# schematic-incomplete.net
KiCad netlist of a schematic drawn in EAGLE
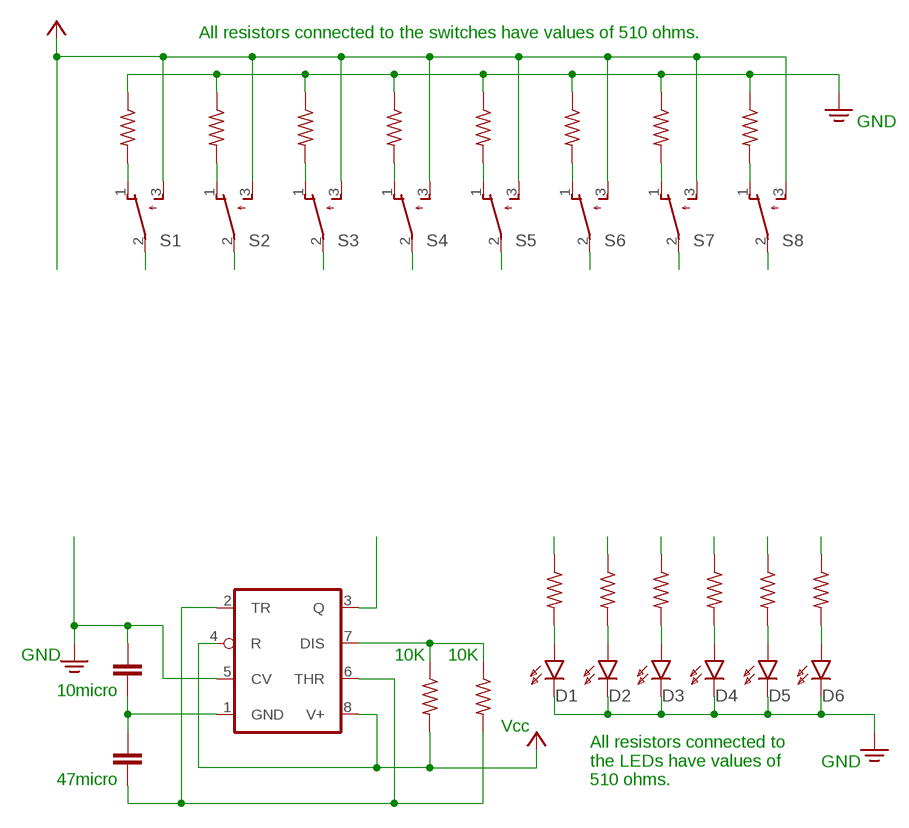
[diagram p0: schematic, sheet 1]

(export (version "E")
  (design (tool "Eeschema 10.0.6"))
  (components
    (comp (ref "10K")
      (value "R-US_0204/7")
      (footprint "eagle-import:0204_7")
      (libsource (lib "eagle-import") (part "R-US_0204/7"))
    )
    (comp (ref "CX1")
      (value "CXXC15B8")
      (footprint "eagle-import:XC15B8")
      (libsource (lib "eagle-import") (part "CXXC15B8"))
    )
    (comp (ref "CX2")
      (value "CXXC15B8")
      (footprint "eagle-import:XC15B8")
      (libsource (lib "eagle-import") (part "CXXC15B8"))
    )
    (comp (ref "D1")
      (value "HLMP6")
      (footprint "eagle-import:HLMP6")
      (fields (field (name "MF") "AGILENT TECHNOLOGIES") (field (name "MPN") "HLMP-6500"))
      (libsource (lib "eagle-import") (part "HLMP6"))
    )
    (comp (ref "D2")
      (value "HLMP6")
      (footprint "eagle-import:HLMP6")
      (fields (field (name "MF") "AGILENT TECHNOLOGIES") (field (name "MPN") "HLMP-6500"))
      (libsource (lib "eagle-import") (part "HLMP6"))
    )
    (comp (ref "D3")
      (value "HLMP6")
      (footprint "eagle-import:HLMP6")
      (fields (field (name "MF") "AGILENT TECHNOLOGIES") (field (name "MPN") "HLMP-6500"))
      (libsource (lib "eagle-import") (part "HLMP6"))
    )
    (comp (ref "D4")
      (value "HLMP6")
      (footprint "eagle-import:HLMP6")
      (fields (field (name "MF") "AGILENT TECHNOLOGIES") (field (name "MPN") "HLMP-6500"))
      (libsource (lib "eagle-import") (part "HLMP6"))
    )
    (comp (ref "D5")
      (value "HLMP6")
      (footprint "eagle-import:HLMP6")
      (fields (field (name "MF") "AGILENT TECHNOLOGIES") (field (name "MPN") "HLMP-6500"))
      (libsource (lib "eagle-import") (part "HLMP6"))
    )
    (comp (ref "D6")
      (value "HLMP6")
      (footprint "eagle-import:HLMP6")
      (fields (field (name "MF") "AGILENT TECHNOLOGIES") (field (name "MPN") "HLMP-6500"))
      (libsource (lib "eagle-import") (part "HLMP6"))
    )
    (comp (ref "IC1")
      (value "LM555N")
      (footprint "eagle-import:DIL08")
      (libsource (lib "eagle-import") (part "555NLM"))
    )
    (comp (ref "R1")
      (value "R-US_0204/7")
      (footprint "eagle-import:0204_7")
      (libsource (lib "eagle-import") (part "R-US_0204/7"))
    )
    (comp (ref "R2")
      (value "R-US_0204/7")
      (footprint "eagle-import:0204_7")
      (libsource (lib "eagle-import") (part "R-US_0204/7"))
    )
    (comp (ref "R3")
      (value "R-US_0204/7")
      (footprint "eagle-import:0204_7")
      (libsource (lib "eagle-import") (part "R-US_0204/7"))
    )
    (comp (ref "R4")
      (value "R-US_0204/7")
      (footprint "eagle-import:0204_7")
      (libsource (lib "eagle-import") (part "R-US_0204/7"))
    )
    (comp (ref "R5")
      (value "R-US_0204/7")
      (footprint "eagle-import:0204_7")
      (libsource (lib "eagle-import") (part "R-US_0204/7"))
    )
    (comp (ref "R6")
      (value "R-US_0204/7")
      (footprint "eagle-import:0204_7")
      (libsource (lib "eagle-import") (part "R-US_0204/7"))
    )
    (comp (ref "R7")
      (value "R-US_0204/7")
      (footprint "eagle-import:0204_7")
      (libsource (lib "eagle-import") (part "R-US_0204/7"))
    )
    (comp (ref "R8")
      (value "R-US_0204/7")
      (footprint "eagle-import:0204_7")
      (libsource (lib "eagle-import") (part "R-US_0204/7"))
    )
    (comp (ref "R9")
      (value "R-US_0204/7")
      (footprint "eagle-import:0204_7")
      (libsource (lib "eagle-import") (part "R-US_0204/7"))
    )
    (comp (ref "R10")
      (value "R-US_0204/7")
      (footprint "eagle-import:0204_7")
      (libsource (lib "eagle-import") (part "R-US_0204/7"))
    )
    (comp (ref "R11")
      (value "R-US_0204/7")
      (footprint "eagle-import:0204_7")
      (libsource (lib "eagle-import") (part "R-US_0204/7"))
    )
    (comp (ref "R12")
      (value "R-US_0204/7")
      (footprint "eagle-import:0204_7")
      (libsource (lib "eagle-import") (part "R-US_0204/7"))
    )
    (comp (ref "R13")
      (value "R-US_0204/7")
      (footprint "eagle-import:0204_7")
      (libsource (lib "eagle-import") (part "R-US_0204/7"))
    )
    (comp (ref "R14")
      (value "R-US_0204/7")
      (footprint "eagle-import:0204_7")
      (libsource (lib "eagle-import") (part "R-US_0204/7"))
    )
    (comp (ref "R15")
      (value "R-US_0204/7")
      (footprint "eagle-import:0204_7")
      (libsource (lib "eagle-import") (part "R-US_0204/7"))
    )
    (comp (ref "S1")
      (value "TL32PO")
      (footprint "eagle-import:TL3XPO")
      (libsource (lib "eagle-import") (part "TL32PO"))
    )
    (comp (ref "S2")
      (value "TL32PO")
      (footprint "eagle-import:TL3XPO")
      (libsource (lib "eagle-import") (part "TL32PO"))
    )
    (comp (ref "S3")
      (value "TL32PO")
      (footprint "eagle-import:TL3XPO")
      (libsource (lib "eagle-import") (part "TL32PO"))
    )
    (comp (ref "S4")
      (value "TL32PO")
      (footprint "eagle-import:TL3XPO")
      (libsource (lib "eagle-import") (part "TL32PO"))
    )
    (comp (ref "S5")
      (value "TL32PO")
      (footprint "eagle-import:TL3XPO")
      (libsource (lib "eagle-import") (part "TL32PO"))
    )
    (comp (ref "S6")
      (value "TL32PO")
      (footprint "eagle-import:TL3XPO")
      (libsource (lib "eagle-import") (part "TL32PO"))
    )
    (comp (ref "S7")
      (value "TL32PO")
      (footprint "eagle-import:TL3XPO")
      (libsource (lib "eagle-import") (part "TL32PO"))
    )
    (comp (ref "S8")
      (value "TL32PO")
      (footprint "eagle-import:TL3XPO")
      (libsource (lib "eagle-import") (part "TL32PO"))
    )
  )
  (nets
    (net (code "1") (name "Net-(D1-PadA)") (class "Default")
      (node (ref "D1") (pin "A") (pinfunction "A_A") (pintype "passive"))
      (node (ref "R10") (pin "2") (pinfunction "2_2") (pintype "passive"))
    )
    (net (code "2") (name "Net-(D2-PadA)") (class "Default")
      (node (ref "D2") (pin "A") (pinfunction "A_A") (pintype "passive"))
      (node (ref "R11") (pin "2") (pinfunction "2_2") (pintype "passive"))
    )
    (net (code "3") (name "Net-(D3-PadA)") (class "Default")
      (node (ref "D3") (pin "A") (pinfunction "A_A") (pintype "passive"))
      (node (ref "R12") (pin "2") (pinfunction "2_2") (pintype "passive"))
    )
    (net (code "4") (name "Net-(D4-PadA)") (class "Default")
      (node (ref "D4") (pin "A") (pinfunction "A_A") (pintype "passive"))
      (node (ref "R13") (pin "2") (pinfunction "2_2") (pintype "passive"))
    )
    (net (code "5") (name "Net-(D5-PadA)") (class "Default")
      (node (ref "D5") (pin "A") (pinfunction "A_A") (pintype "passive"))
      (node (ref "R14") (pin "2") (pinfunction "2_2") (pintype "passive"))
    )
    (net (code "6") (name "Net-(D6-PadA)") (class "Default")
      (node (ref "D6") (pin "A") (pinfunction "A_A") (pintype "passive"))
      (node (ref "R15") (pin "2") (pinfunction "2_2") (pintype "passive"))
    )
    (net (code "7") (name "Net-(IC1-DIS)") (class "Default")
      (node (ref "10K") (pin "1") (pinfunction "1_1") (pintype "passive"))
      (node (ref "IC1") (pin "7") (pinfunction "DIS_7") (pintype "input"))
      (node (ref "R2") (pin "1") (pinfunction "1_1") (pintype "passive"))
    )
    (net (code "8") (name "Net-(IC1-GND)") (class "Default")
      (node (ref "CX1") (pin "2") (pinfunction "2_2") (pintype "passive"))
      (node (ref "CX2") (pin "1") (pinfunction "1_1") (pintype "passive"))
      (node (ref "IC1") (pin "1") (pinfunction "GND_1") (pintype "power_in"))
    )
    (net (code "9") (name "Net-(IC1-THR)") (class "Default")
      (node (ref "CX1") (pin "1") (pinfunction "1_1") (pintype "passive"))
      (node (ref "IC1") (pin "2") (pinfunction "TR_2") (pintype "input"))
      (node (ref "IC1") (pin "6") (pinfunction "THR_6") (pintype "input"))
      (node (ref "R2") (pin "2") (pinfunction "2_2") (pintype "passive"))
    )
    (net (code "10") (name "Net-(S1-O)") (class "Default")
      (node (ref "R1") (pin "2") (pinfunction "2_2") (pintype "passive"))
      (node (ref "S1") (pin "1") (pinfunction "O_1") (pintype "passive"))
    )
    (net (code "11") (name "Net-(S2-O)") (class "Default")
      (node (ref "R3") (pin "2") (pinfunction "2_2") (pintype "passive"))
      (node (ref "S2") (pin "1") (pinfunction "O_1") (pintype "passive"))
    )
    (net (code "12") (name "Net-(S3-O)") (class "Default")
      (node (ref "R4") (pin "2") (pinfunction "2_2") (pintype "passive"))
      (node (ref "S3") (pin "1") (pinfunction "O_1") (pintype "passive"))
    )
    (net (code "13") (name "Net-(S4-O)") (class "Default")
      (node (ref "R5") (pin "2") (pinfunction "2_2") (pintype "passive"))
      (node (ref "S4") (pin "1") (pinfunction "O_1") (pintype "passive"))
    )
    (net (code "14") (name "Net-(S5-O)") (class "Default")
      (node (ref "R6") (pin "2") (pinfunction "2_2") (pintype "passive"))
      (node (ref "S5") (pin "1") (pinfunction "O_1") (pintype "passive"))
    )
    (net (code "15") (name "Net-(S6-O)") (class "Default")
      (node (ref "R7") (pin "2") (pinfunction "2_2") (pintype "passive"))
      (node (ref "S6") (pin "1") (pinfunction "O_1") (pintype "passive"))
    )
    (net (code "16") (name "Net-(S7-O)") (class "Default")
      (node (ref "R8") (pin "2") (pinfunction "2_2") (pintype "passive"))
      (node (ref "S7") (pin "1") (pinfunction "O_1") (pintype "passive"))
    )
    (net (code "17") (name "Net-(S8-O)") (class "Default")
      (node (ref "R9") (pin "2") (pinfunction "2_2") (pintype "passive"))
      (node (ref "S8") (pin "1") (pinfunction "O_1") (pintype "passive"))
    )
    (net (code "18") (name "PE") (class "Default")
      (node (ref "CX2") (pin "2") (pinfunction "2_2") (pintype "passive"))
      (node (ref "D1") (pin "K") (pinfunction "K_K") (pintype "passive"))
      (node (ref "D2") (pin "K") (pinfunction "K_K") (pintype "passive"))
      (node (ref "D3") (pin "K") (pinfunction "K_K") (pintype "passive"))
      (node (ref "D4") (pin "K") (pinfunction "K_K") (pintype "passive"))
      (node (ref "D5") (pin "K") (pinfunction "K_K") (pintype "passive"))
      (node (ref "D6") (pin "K") (pinfunction "K_K") (pintype "passive"))
      (node (ref "IC1") (pin "5") (pinfunction "CV_5") (pintype "input"))
      (node (ref "R1") (pin "1") (pinfunction "1_1") (pintype "passive"))
      (node (ref "R3") (pin "1") (pinfunction "1_1") (pintype "passive"))
      (node (ref "R4") (pin "1") (pinfunction "1_1") (pintype "passive"))
      (node (ref "R5") (pin "1") (pinfunction "1_1") (pintype "passive"))
      (node (ref "R6") (pin "1") (pinfunction "1_1") (pintype "passive"))
      (node (ref "R7") (pin "1") (pinfunction "1_1") (pintype "passive"))
      (node (ref "R8") (pin "1") (pinfunction "1_1") (pintype "passive"))
      (node (ref "R9") (pin "1") (pinfunction "1_1") (pintype "passive"))
    )
    (net (code "19") (name "V+") (class "Default")
      (node (ref "10K") (pin "2") (pinfunction "2_2") (pintype "passive"))
      (node (ref "IC1") (pin "4") (pinfunction "R_4") (pintype "input"))
      (node (ref "IC1") (pin "8") (pinfunction "V+_8") (pintype "power_in"))
      (node (ref "S1") (pin "3") (pinfunction "S_3") (pintype "passive"))
      (node (ref "S2") (pin "3") (pinfunction "S_3") (pintype "passive"))
      (node (ref "S3") (pin "3") (pinfunction "S_3") (pintype "passive"))
      (node (ref "S4") (pin "3") (pinfunction "S_3") (pintype "passive"))
      (node (ref "S5") (pin "3") (pinfunction "S_3") (pintype "passive"))
      (node (ref "S6") (pin "3") (pinfunction "S_3") (pintype "passive"))
      (node (ref "S7") (pin "3") (pinfunction "S_3") (pintype "passive"))
      (node (ref "S8") (pin "3") (pinfunction "S_3") (pintype "passive"))
    )
    (net (code "20") (name "unconnected-(IC1-Q-Pad3)") (class "Default")
      (node (ref "IC1") (pin "3") (pinfunction "Q_3") (pintype "output"))
    )
    (net (code "21") (name "unconnected-(R10-Pad1)") (class "Default")
      (node (ref "R10") (pin "1") (pinfunction "1_1") (pintype "passive"))
    )
    (net (code "22") (name "unconnected-(R11-Pad1)") (class "Default")
      (node (ref "R11") (pin "1") (pinfunction "1_1") (pintype "passive"))
    )
    (net (code "23") (name "unconnected-(R12-Pad1)") (class "Default")
      (node (ref "R12") (pin "1") (pinfunction "1_1") (pintype "passive"))
    )
    (net (code "24") (name "unconnected-(R13-Pad1)") (class "Default")
      (node (ref "R13") (pin "1") (pinfunction "1_1") (pintype "passive"))
    )
    (net (code "25") (name "unconnected-(R14-Pad1)") (class "Default")
      (node (ref "R14") (pin "1") (pinfunction "1_1") (pintype "passive"))
    )
    (net (code "26") (name "unconnected-(R15-Pad1)") (class "Default")
      (node (ref "R15") (pin "1") (pinfunction "1_1") (pintype "passive"))
    )
    (net (code "27") (name "unconnected-(S1-P-Pad2)") (class "Default")
      (node (ref "S1") (pin "2") (pinfunction "P_2") (pintype "passive"))
    )
    (net (code "28") (name "unconnected-(S2-P-Pad2)") (class "Default")
      (node (ref "S2") (pin "2") (pinfunction "P_2") (pintype "passive"))
    )
    (net (code "29") (name "unconnected-(S3-P-Pad2)") (class "Default")
      (node (ref "S3") (pin "2") (pinfunction "P_2") (pintype "passive"))
    )
    (net (code "30") (name "unconnected-(S4-P-Pad2)") (class "Default")
      (node (ref "S4") (pin "2") (pinfunction "P_2") (pintype "passive"))
    )
    (net (code "31") (name "unconnected-(S5-P-Pad2)") (class "Default")
      (node (ref "S5") (pin "2") (pinfunction "P_2") (pintype "passive"))
    )
    (net (code "32") (name "unconnected-(S6-P-Pad2)") (class "Default")
      (node (ref "S6") (pin "2") (pinfunction "P_2") (pintype "passive"))
    )
    (net (code "33") (name "unconnected-(S7-P-Pad2)") (class "Default")
      (node (ref "S7") (pin "2") (pinfunction "P_2") (pintype "passive"))
    )
    (net (code "34") (name "unconnected-(S8-P-Pad2)") (class "Default")
      (node (ref "S8") (pin "2") (pinfunction "P_2") (pintype "passive"))
    )
  )
)
